# 2_ZEGAR_NIXIE.net
KiCad netlist of a schematic drawn in EAGLE
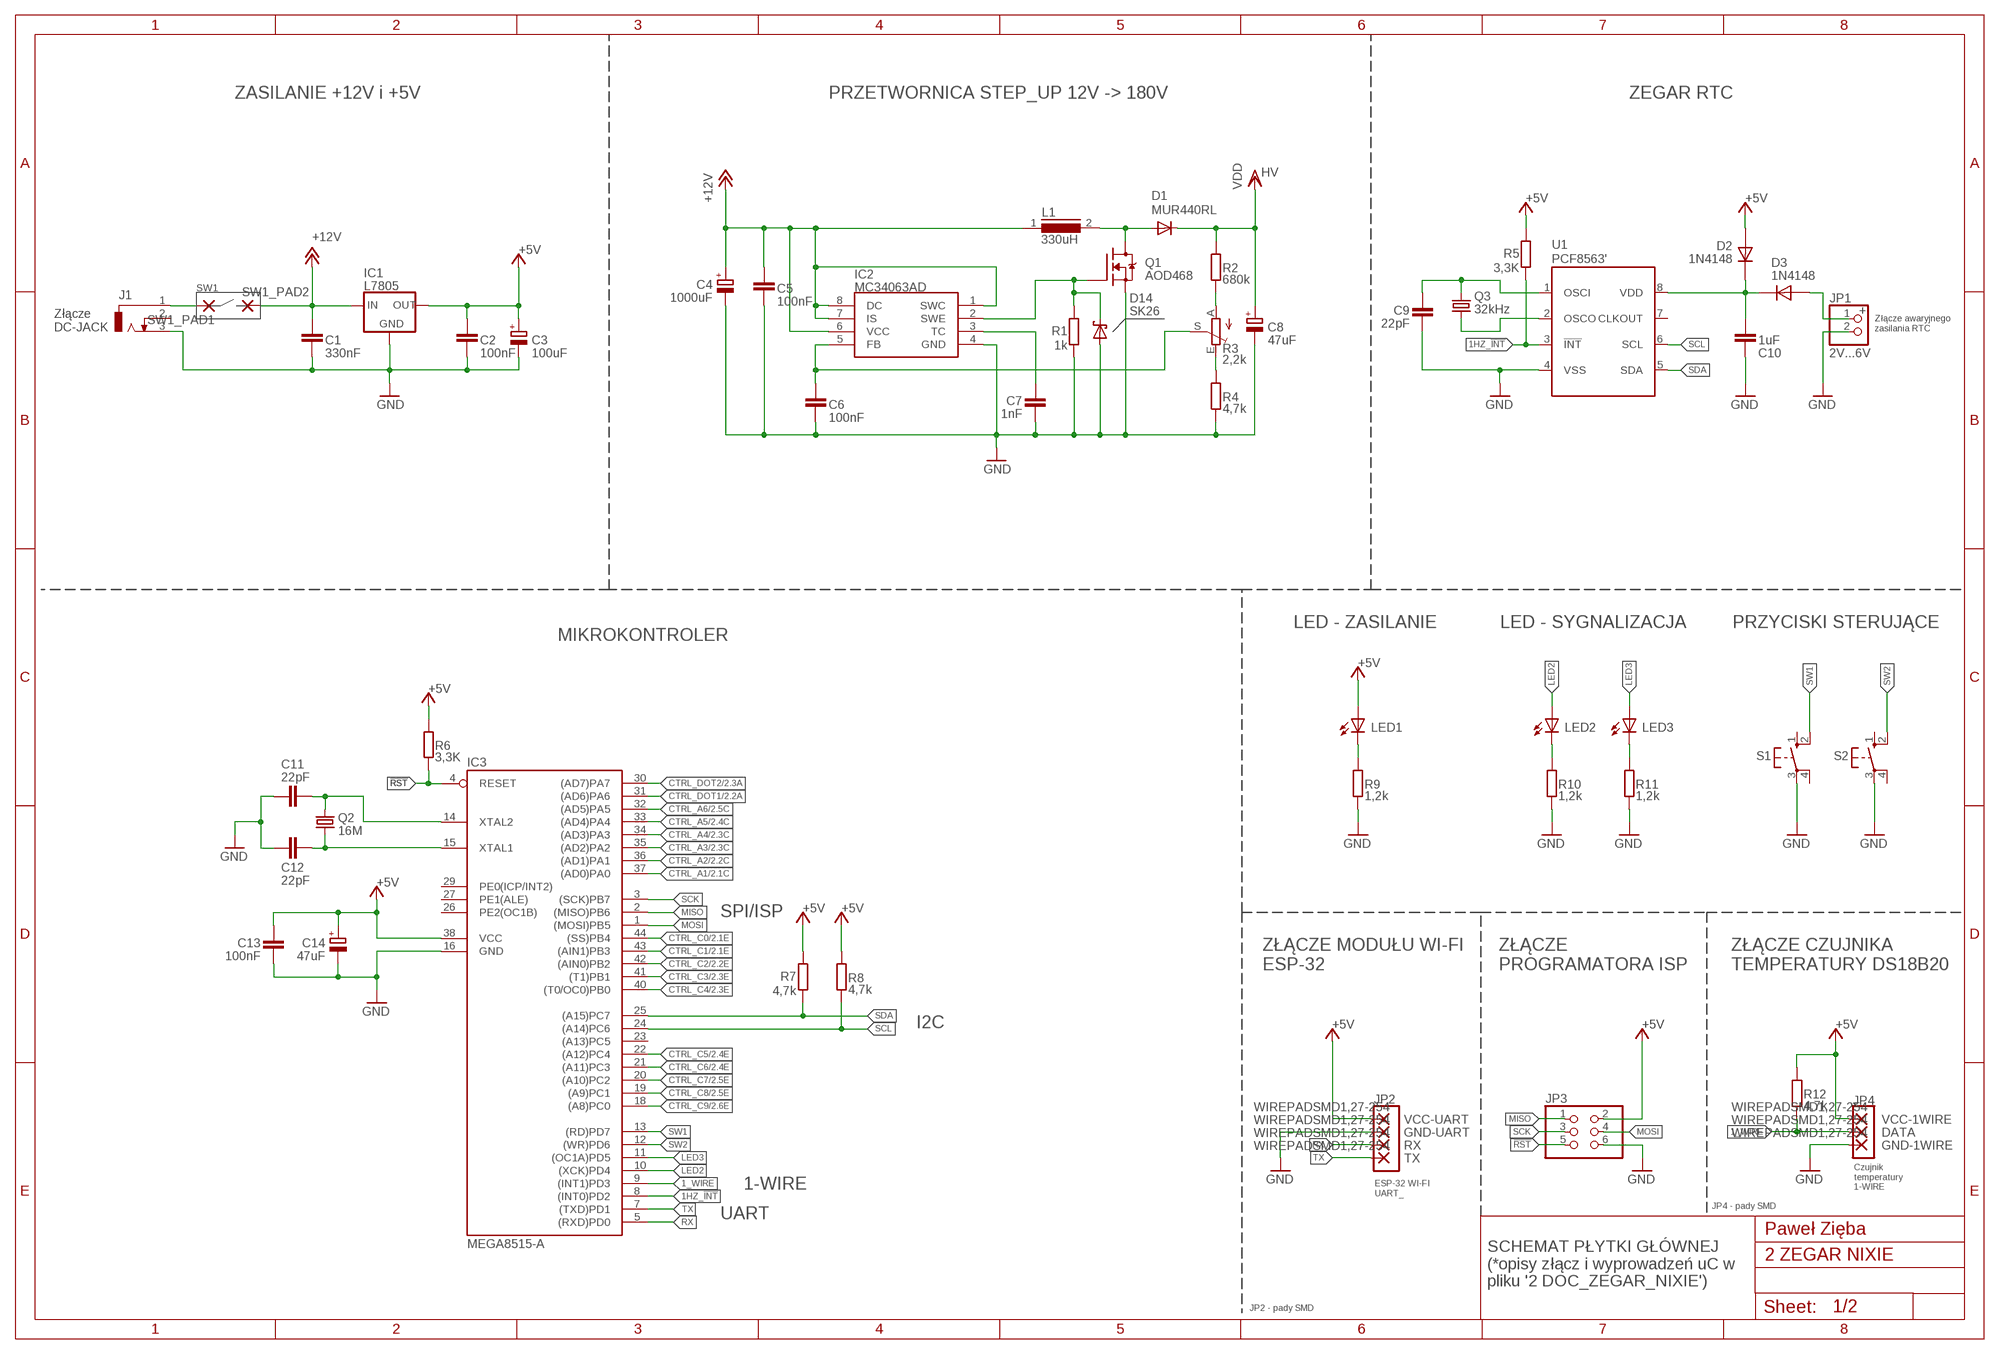
[diagram p0: schematic, sheet 1]
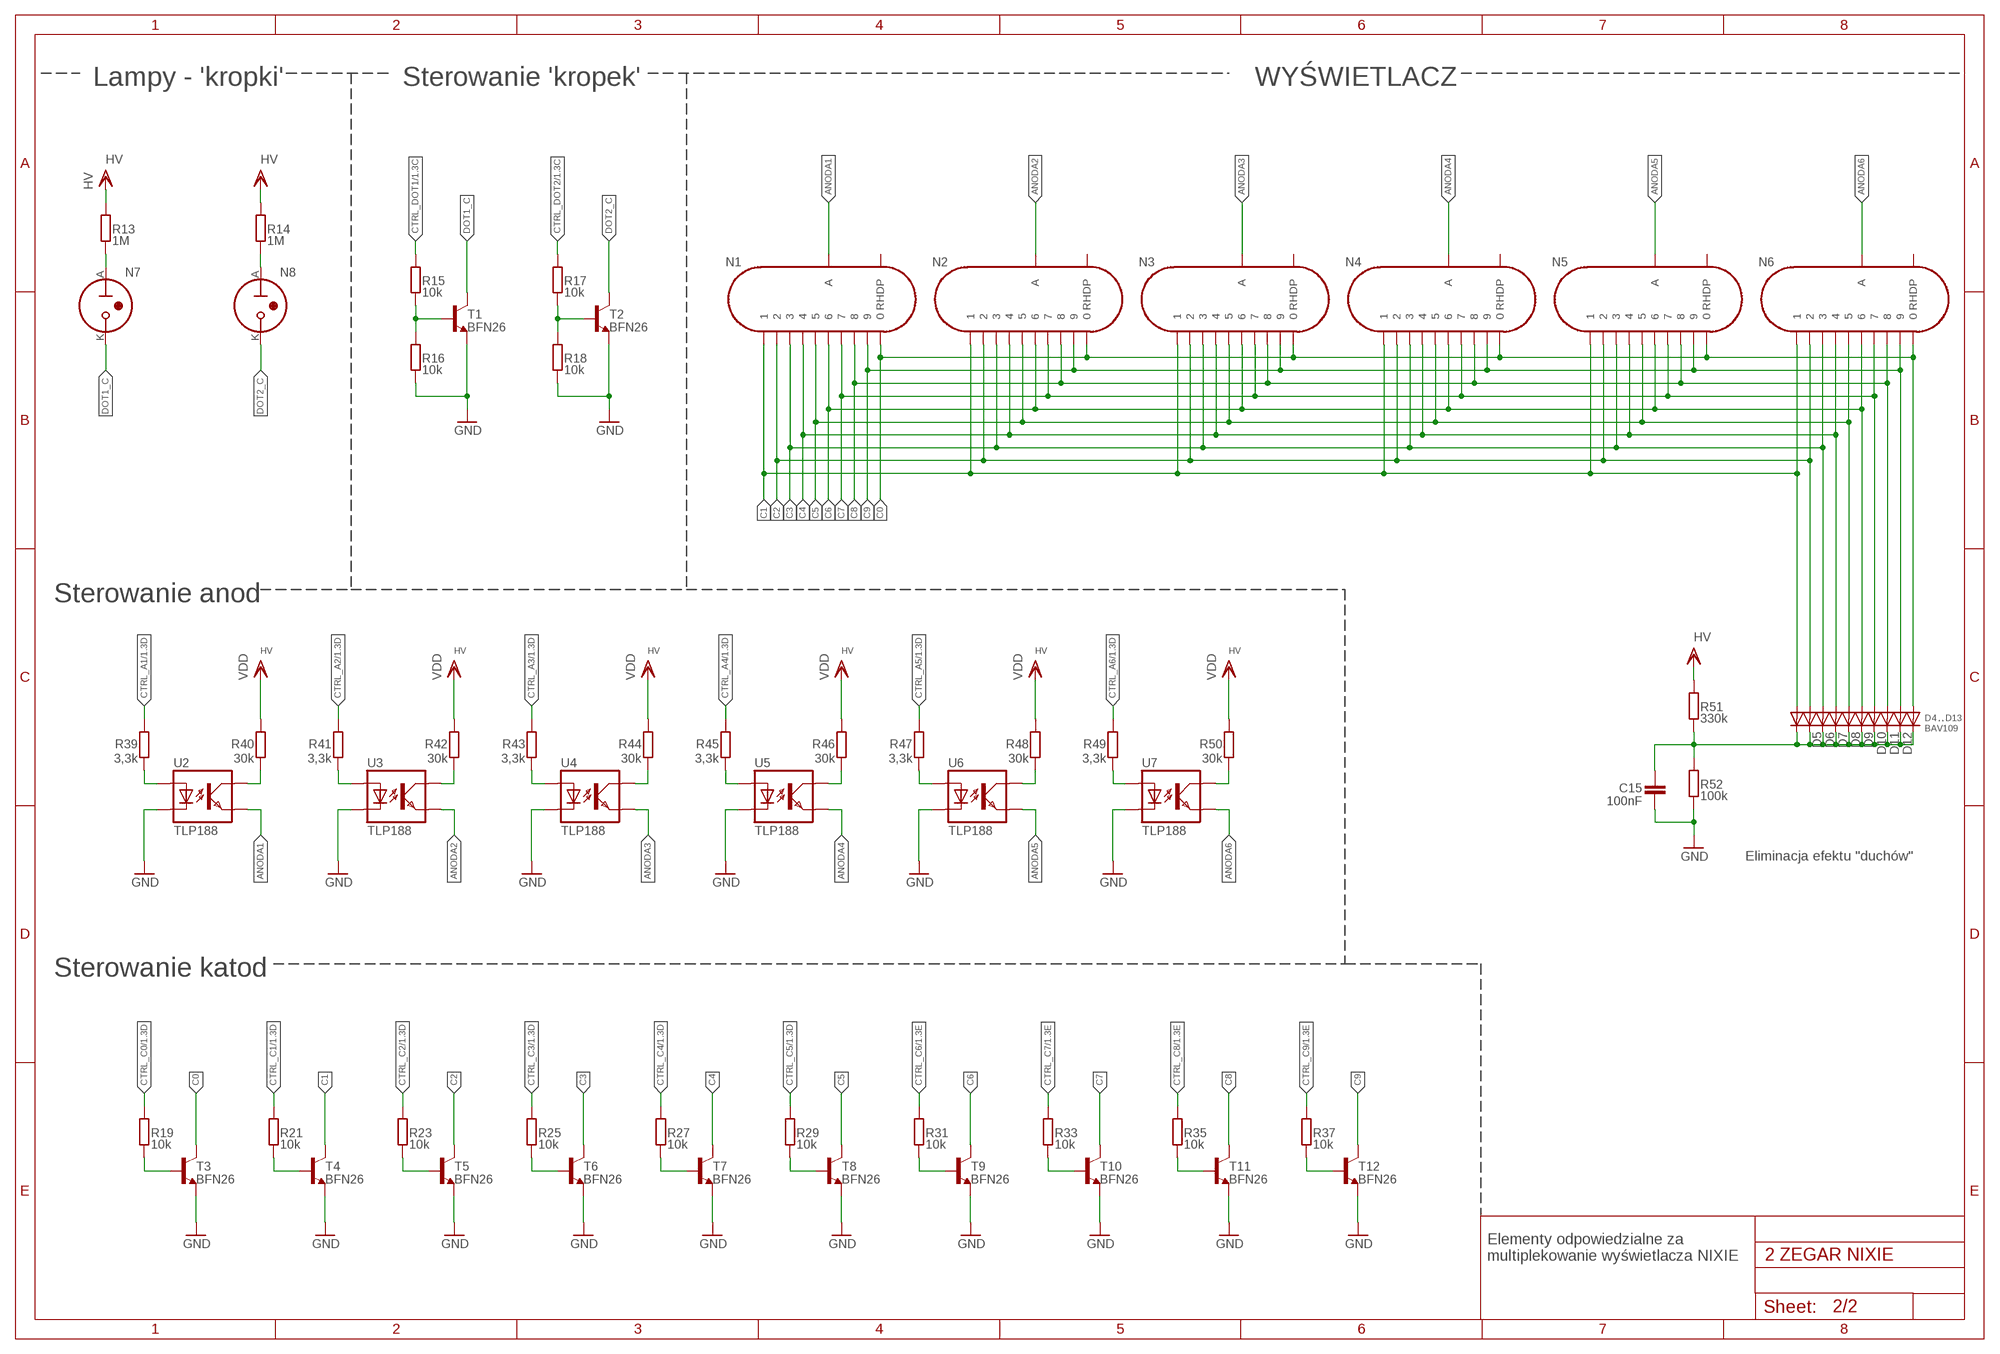
[diagram p1: schematic, sheet 2]

(export (version "E")
  (design (tool "Eeschema 10.0.6"))
  (components
    (comp (ref "C1")
      (value "330nF")
      (footprint "eagle-import:C1206")
      (libsource (lib "eagle-import") (part "C-EUC1206"))
    )
    (comp (ref "C2")
      (value "100nF")
      (footprint "eagle-import:C1206")
      (libsource (lib "eagle-import") (part "C-EUC1206"))
    )
    (comp (ref "C3")
      (value "100uF")
      (footprint "eagle-import:E5-10,5")
      (libsource (lib "eagle-import") (part "CPOL-EUE5-10.5"))
    )
    (comp (ref "C4")
      (value "1000uF")
      (footprint "eagle-import:E5-10,5")
      (libsource (lib "eagle-import") (part "CPOL-EUE5-10.5"))
    )
    (comp (ref "C5")
      (value "100nF")
      (footprint "eagle-import:C1206")
      (libsource (lib "eagle-import") (part "C-EUC1206"))
    )
    (comp (ref "C6")
      (value "100nF")
      (footprint "eagle-import:C1206")
      (libsource (lib "eagle-import") (part "C-EUC1206"))
    )
    (comp (ref "C7")
      (value "1nF")
      (footprint "eagle-import:C1206")
      (libsource (lib "eagle-import") (part "C-EUC1206"))
    )
    (comp (ref "C8")
      (value "47uF")
      (footprint "eagle-import:E5-13")
      (libsource (lib "eagle-import") (part "CPOL-EUE5-13"))
    )
    (comp (ref "C9")
      (value "22pF")
      (footprint "eagle-import:C1206")
      (libsource (lib "eagle-import") (part "C-EUC1206"))
    )
    (comp (ref "C10")
      (value "1uF")
      (footprint "eagle-import:C1206")
      (libsource (lib "eagle-import") (part "C-EUC1206"))
    )
    (comp (ref "C11")
      (value "22pF")
      (footprint "eagle-import:C1206")
      (libsource (lib "eagle-import") (part "C-EUC1206"))
    )
    (comp (ref "C12")
      (value "22pF")
      (footprint "eagle-import:C1206")
      (libsource (lib "eagle-import") (part "C-EUC1206"))
    )
    (comp (ref "C13")
      (value "100nF")
      (footprint "eagle-import:C1206")
      (libsource (lib "eagle-import") (part "C-EUC1206"))
    )
    (comp (ref "C14")
      (value "47uF")
      (footprint "eagle-import:UD-6,3X5,8_NICHICON")
      (libsource (lib "eagle-import") (part "CPOL-EUUD-6,3X8,8"))
    )
    (comp (ref "D1")
      (value "MUR440RL")
      (footprint "eagle-import:C2673")
      (libsource (lib "eagle-import") (part "MUR440RL"))
    )
    (comp (ref "D2")
      (value "1N4148")
      (footprint "eagle-import:D1206")
      (libsource (lib "eagle-import") (part "N14148'"))
    )
    (comp (ref "D3")
      (value "1N4148")
      (footprint "eagle-import:D1206")
      (libsource (lib "eagle-import") (part "N14148'"))
    )
    (comp (ref "D14")
      (value "SK26")
      (footprint "eagle-import:SMB")
      (libsource (lib "eagle-import") (part "SCHOTTKY-DIODESMD"))
    )
    (comp (ref "DATA")
      (value "WIREPADSMD1,27-254")
      (footprint "eagle-import:SMD1,27-2,54")
      (libsource (lib "eagle-import") (part "WIREPADSMD1,27-254"))
    )
    (comp (ref "GND-1WIRE")
      (value "WIREPADSMD1,27-254")
      (footprint "eagle-import:SMD1,27-2,54")
      (libsource (lib "eagle-import") (part "WIREPADSMD1,27-254"))
    )
    (comp (ref "GND-UART")
      (value "WIREPADSMD1,27-254")
      (footprint "eagle-import:SMD1,27-2,54")
      (libsource (lib "eagle-import") (part "WIREPADSMD1,27-254"))
    )
    (comp (ref "IC1")
      (value "L7805")
      (footprint "eagle-import:DPAK")
      (libsource (lib "eagle-import") (part "L78-ST'"))
    )
    (comp (ref "IC2")
      (value "MC34063AD")
      (footprint "eagle-import:SOIC8")
      (libsource (lib "eagle-import") (part "MC34063AD"))
    )
    (comp (ref "IC3")
      (value "MEGA8515-A")
      (footprint "eagle-import:TQFP44")
      (fields (field (name "MPN") "ATMEGA8515-16AU"))
      (libsource (lib "eagle-import") (part "MEGA8515-A"))
    )
    (comp (ref "J1")
      (value "DCJ0303")
      (footprint "eagle-import:DCJ0303")
      (libsource (lib "eagle-import") (part "DCJ0303"))
    )
    (comp (ref "JP1")
      (value "2V...6V")
      (footprint "eagle-import:1X02")
      (libsource (lib "eagle-import") (part "PINHD-1X2"))
    )
    (comp (ref "JP3")
      (value "PINHD-2X3")
      (footprint "eagle-import:2X03")
      (libsource (lib "eagle-import") (part "PINHD-2X3"))
    )
    (comp (ref "L1")
      (value "330uH")
      (footprint "eagle-import:SFT830D")
      (libsource (lib "eagle-import") (part "SFT830D"))
    )
    (comp (ref "LED1")
      (value "LED_E")
      (footprint "eagle-import:LED_1206")
      (libsource (lib "eagle-import") (part "LED_E"))
    )
    (comp (ref "LED2")
      (value "LED_E")
      (footprint "eagle-import:LED_1206")
      (libsource (lib "eagle-import") (part "LED_E"))
    )
    (comp (ref "LED3")
      (value "LED_E")
      (footprint "eagle-import:LED_1206")
      (libsource (lib "eagle-import") (part "LED_E"))
    )
    (comp (ref "Q1")
      (value "AOD468")
      (footprint "eagle-import:DPAK-TO252")
      (libsource (lib "eagle-import") (part "AOD468"))
    )
    (comp (ref "Q2")
      (value "16M")
      (footprint "eagle-import:2.5X2.0_KX-6")
      (libsource (lib "eagle-import") (part "KX-6"))
    )
    (comp (ref "Q3")
      (value "32kHz")
      (footprint "eagle-import:TC26H")
      (libsource (lib "eagle-import") (part "CRYSTALTC26H"))
    )
    (comp (ref "R1")
      (value "1k")
      (footprint "eagle-import:R0805")
      (libsource (lib "eagle-import") (part "R-EU_R0805"))
    )
    (comp (ref "R2")
      (value "680k")
      (footprint "eagle-import:R0805")
      (libsource (lib "eagle-import") (part "R-EU_R0805"))
    )
    (comp (ref "R3")
      (value "2,2k")
      (footprint "eagle-import:CA6V")
      (libsource (lib "eagle-import") (part "TRIM_EU-CA6V"))
    )
    (comp (ref "R4")
      (value "4,7k")
      (footprint "eagle-import:R0805")
      (libsource (lib "eagle-import") (part "R-EU_R0805"))
    )
    (comp (ref "R5")
      (value "3,3K")
      (footprint "eagle-import:R1206")
      (libsource (lib "eagle-import") (part "R-EU_R1206"))
    )
    (comp (ref "R6")
      (value "3,3K")
      (footprint "eagle-import:R1206")
      (libsource (lib "eagle-import") (part "R-EU_R1206"))
    )
    (comp (ref "R7")
      (value "4,7k")
      (footprint "eagle-import:R1206")
      (libsource (lib "eagle-import") (part "R-EU_R1206"))
    )
    (comp (ref "R8")
      (value "4,7k")
      (footprint "eagle-import:R1206")
      (libsource (lib "eagle-import") (part "R-EU_R1206"))
    )
    (comp (ref "R9")
      (value "1,2k")
      (footprint "eagle-import:R1206")
      (libsource (lib "eagle-import") (part "R-EU_R1206"))
    )
    (comp (ref "R10")
      (value "1,2k")
      (footprint "eagle-import:R1206")
      (libsource (lib "eagle-import") (part "R-EU_R1206"))
    )
    (comp (ref "R11")
      (value "1,2k")
      (footprint "eagle-import:R1206")
      (libsource (lib "eagle-import") (part "R-EU_R1206"))
    )
    (comp (ref "R12")
      (value "4,7k")
      (footprint "eagle-import:R1206")
      (libsource (lib "eagle-import") (part "R-EU_R1206"))
    )
    (comp (ref "RX")
      (value "WIREPADSMD1,27-254")
      (footprint "eagle-import:SMD1,27-2,54")
      (libsource (lib "eagle-import") (part "WIREPADSMD1,27-254"))
    )
    (comp (ref "S1")
      (value "10-XX")
      (footprint "eagle-import:B3F-10XX")
      (fields (field (name "MPN") "B3F-1000"))
      (libsource (lib "eagle-import") (part "10-XX"))
    )
    (comp (ref "S2")
      (value "10-XX")
      (footprint "eagle-import:B3F-10XX")
      (fields (field (name "MPN") "B3F-1000"))
      (libsource (lib "eagle-import") (part "10-XX"))
    )
    (comp (ref "SW1_PAD1")
      (value "3,81/1,4")
      (footprint "eagle-import:3,81_1,4")
      (libsource (lib "eagle-import") (part "3,81/1,4"))
    )
    (comp (ref "SW1_PAD2")
      (value "3,81/1,4")
      (footprint "eagle-import:3,81_1,4")
      (libsource (lib "eagle-import") (part "3,81/1,4"))
    )
    (comp (ref "TX")
      (value "WIREPADSMD1,27-254")
      (footprint "eagle-import:SMD1,27-2,54")
      (libsource (lib "eagle-import") (part "WIREPADSMD1,27-254"))
    )
    (comp (ref "U1")
      (value "PCF8563'")
      (footprint "eagle-import:SO08-IRF")
      (libsource (lib "eagle-import") (part "PCF8563'"))
    )
    (comp (ref "VCC-1WIRE")
      (value "WIREPADSMD1,27-254")
      (footprint "eagle-import:SMD1,27-2,54")
      (libsource (lib "eagle-import") (part "WIREPADSMD1,27-254"))
    )
    (comp (ref "VCC-UART")
      (value "WIREPADSMD1,27-254")
      (footprint "eagle-import:SMD1,27-2,54")
      (libsource (lib "eagle-import") (part "WIREPADSMD1,27-254"))
    )
    (comp (ref "C15")
      (value "100nF")
      (footprint "eagle-import:C1206")
      (libsource (lib "eagle-import") (part "C-EUC1206"))
    )
    (comp (ref "D4")
      (value "DIODE-MINIMELF")
      (footprint "eagle-import:MINIMELF")
      (libsource (lib "eagle-import") (part "DIODE-MINIMELF"))
    )
    (comp (ref "D5")
      (value "DIODE-MINIMELF")
      (footprint "eagle-import:MINIMELF")
      (libsource (lib "eagle-import") (part "DIODE-MINIMELF"))
    )
    (comp (ref "D6")
      (value "DIODE-MINIMELF")
      (footprint "eagle-import:MINIMELF")
      (libsource (lib "eagle-import") (part "DIODE-MINIMELF"))
    )
    (comp (ref "D7")
      (value "DIODE-MINIMELF")
      (footprint "eagle-import:MINIMELF")
      (libsource (lib "eagle-import") (part "DIODE-MINIMELF"))
    )
    (comp (ref "D8")
      (value "DIODE-MINIMELF")
      (footprint "eagle-import:MINIMELF")
      (libsource (lib "eagle-import") (part "DIODE-MINIMELF"))
    )
    (comp (ref "D9")
      (value "DIODE-MINIMELF")
      (footprint "eagle-import:MINIMELF")
      (libsource (lib "eagle-import") (part "DIODE-MINIMELF"))
    )
    (comp (ref "D10")
      (value "DIODE-MINIMELF")
      (footprint "eagle-import:MINIMELF")
      (libsource (lib "eagle-import") (part "DIODE-MINIMELF"))
    )
    (comp (ref "D11")
      (value "DIODE-MINIMELF")
      (footprint "eagle-import:MINIMELF")
      (libsource (lib "eagle-import") (part "DIODE-MINIMELF"))
    )
    (comp (ref "D12")
      (value "DIODE-MINIMELF")
      (footprint "eagle-import:MINIMELF")
      (libsource (lib "eagle-import") (part "DIODE-MINIMELF"))
    )
    (comp (ref "D13")
      (value "BAV109")
      (footprint "eagle-import:MINIMELF")
      (libsource (lib "eagle-import") (part "DIODE-MINIMELF"))
    )
    (comp (ref "N1")
      (value "IN-8-2")
      (footprint "eagle-import:IN-8-2")
      (libsource (lib "eagle-import") (part "IN-8-2"))
    )
    (comp (ref "N2")
      (value "IN-8-2")
      (footprint "eagle-import:IN-8-2")
      (libsource (lib "eagle-import") (part "IN-8-2"))
    )
    (comp (ref "N3")
      (value "IN-8-2")
      (footprint "eagle-import:IN-8-2")
      (libsource (lib "eagle-import") (part "IN-8-2"))
    )
    (comp (ref "N4")
      (value "IN-8-2")
      (footprint "eagle-import:IN-8-2")
      (libsource (lib "eagle-import") (part "IN-8-2"))
    )
    (comp (ref "N5")
      (value "IN-8-2")
      (footprint "eagle-import:IN-8-2")
      (libsource (lib "eagle-import") (part "IN-8-2"))
    )
    (comp (ref "N6")
      (value "IN-8-2")
      (footprint "eagle-import:IN-8-2")
      (libsource (lib "eagle-import") (part "IN-8-2"))
    )
    (comp (ref "N7")
      (value "IN-3")
      (footprint "eagle-import:IN-3")
      (libsource (lib "eagle-import") (part "IN-3"))
    )
    (comp (ref "N8")
      (value "IN-3")
      (footprint "eagle-import:IN-3")
      (libsource (lib "eagle-import") (part "IN-3"))
    )
    (comp (ref "R13")
      (value "1M")
      (footprint "eagle-import:R1206")
      (libsource (lib "eagle-import") (part "R-EU_R1206"))
    )
    (comp (ref "R14")
      (value "1M")
      (footprint "eagle-import:R1206")
      (libsource (lib "eagle-import") (part "R-EU_R1206"))
    )
    (comp (ref "R15")
      (value "10k")
      (footprint "eagle-import:R0805")
      (libsource (lib "eagle-import") (part "R-EU_R0805"))
    )
    (comp (ref "R16")
      (value "10k")
      (footprint "eagle-import:R0805")
      (libsource (lib "eagle-import") (part "R-EU_R0805"))
    )
    (comp (ref "R17")
      (value "10k")
      (footprint "eagle-import:R0805")
      (libsource (lib "eagle-import") (part "R-EU_R0805"))
    )
    (comp (ref "R18")
      (value "10k")
      (footprint "eagle-import:R0805")
      (libsource (lib "eagle-import") (part "R-EU_R0805"))
    )
    (comp (ref "R19")
      (value "10k")
      (footprint "eagle-import:R0805")
      (libsource (lib "eagle-import") (part "R-EU_R0805"))
    )
    (comp (ref "R21")
      (value "10k")
      (footprint "eagle-import:R0805")
      (libsource (lib "eagle-import") (part "R-EU_R0805"))
    )
    (comp (ref "R23")
      (value "10k")
      (footprint "eagle-import:R0805")
      (libsource (lib "eagle-import") (part "R-EU_R0805"))
    )
    (comp (ref "R25")
      (value "10k")
      (footprint "eagle-import:R0805")
      (libsource (lib "eagle-import") (part "R-EU_R0805"))
    )
    (comp (ref "R27")
      (value "10k")
      (footprint "eagle-import:R0805")
      (libsource (lib "eagle-import") (part "R-EU_R0805"))
    )
    (comp (ref "R29")
      (value "10k")
      (footprint "eagle-import:R0805")
      (libsource (lib "eagle-import") (part "R-EU_R0805"))
    )
    (comp (ref "R31")
      (value "10k")
      (footprint "eagle-import:R0805")
      (libsource (lib "eagle-import") (part "R-EU_R0805"))
    )
    (comp (ref "R33")
      (value "10k")
      (footprint "eagle-import:R0805")
      (libsource (lib "eagle-import") (part "R-EU_R0805"))
    )
    (comp (ref "R35")
      (value "10k")
      (footprint "eagle-import:R0805")
      (libsource (lib "eagle-import") (part "R-EU_R0805"))
    )
    (comp (ref "R37")
      (value "10k")
      (footprint "eagle-import:R0805")
      (libsource (lib "eagle-import") (part "R-EU_R0805"))
    )
    (comp (ref "R39")
      (value "3,3k")
      (footprint "eagle-import:R0805")
      (libsource (lib "eagle-import") (part "R-EU_R0805"))
    )
    (comp (ref "R40")
      (value "30k")
      (footprint "eagle-import:R1206")
      (libsource (lib "eagle-import") (part "R-EU_R1206"))
    )
    (comp (ref "R41")
      (value "3,3k")
      (footprint "eagle-import:R0805")
      (libsource (lib "eagle-import") (part "R-EU_R0805"))
    )
    (comp (ref "R42")
      (value "30k")
      (footprint "eagle-import:R1206")
      (libsource (lib "eagle-import") (part "R-EU_R1206"))
    )
    (comp (ref "R43")
      (value "3,3k")
      (footprint "eagle-import:R0805")
      (libsource (lib "eagle-import") (part "R-EU_R0805"))
    )
    (comp (ref "R44")
      (value "30k")
      (footprint "eagle-import:R1206")
      (libsource (lib "eagle-import") (part "R-EU_R1206"))
    )
    (comp (ref "R45")
      (value "3,3k")
      (footprint "eagle-import:R0805")
      (libsource (lib "eagle-import") (part "R-EU_R0805"))
    )
    (comp (ref "R46")
      (value "30k")
      (footprint "eagle-import:R1206")
      (libsource (lib "eagle-import") (part "R-EU_R1206"))
    )
    (comp (ref "R47")
      (value "3,3k")
      (footprint "eagle-import:R0805")
      (libsource (lib "eagle-import") (part "R-EU_R0805"))
    )
    (comp (ref "R48")
      (value "30k")
      (footprint "eagle-import:R1206")
      (libsource (lib "eagle-import") (part "R-EU_R1206"))
    )
    (comp (ref "R49")
      (value "3,3k")
      (footprint "eagle-import:R0805")
      (libsource (lib "eagle-import") (part "R-EU_R0805"))
    )
    (comp (ref "R50")
      (value "30k")
      (footprint "eagle-import:R1206")
      (libsource (lib "eagle-import") (part "R-EU_R1206"))
    )
    (comp (ref "R51")
      (value "330k")
      (footprint "eagle-import:R1206")
      (libsource (lib "eagle-import") (part "R-EU_R1206"))
    )
    (comp (ref "R52")
      (value "100k")
      (footprint "eagle-import:R1206")
      (libsource (lib "eagle-import") (part "R-EU_R1206"))
    )
    (comp (ref "T1")
      (value "BFN26")
      (footprint "eagle-import:SOT23-BEC")
      (libsource (lib "eagle-import") (part "BC850SMD"))
    )
    (comp (ref "T2")
      (value "BFN26")
      (footprint "eagle-import:SOT23-BEC")
      (libsource (lib "eagle-import") (part "BC850SMD"))
    )
    (comp (ref "T3")
      (value "BFN26")
      (footprint "eagle-import:SOT23-BEC")
      (libsource (lib "eagle-import") (part "BC850SMD"))
    )
    (comp (ref "T4")
      (value "BFN26")
      (footprint "eagle-import:SOT23-BEC")
      (libsource (lib "eagle-import") (part "BC850SMD"))
    )
    (comp (ref "T5")
      (value "BFN26")
      (footprint "eagle-import:SOT23-BEC")
      (libsource (lib "eagle-import") (part "BC850SMD"))
    )
    (comp (ref "T6")
      (value "BFN26")
      (footprint "eagle-import:SOT23-BEC")
      (libsource (lib "eagle-import") (part "BC850SMD"))
    )
    (comp (ref "T7")
      (value "BFN26")
      (footprint "eagle-import:SOT23-BEC")
      (libsource (lib "eagle-import") (part "BC850SMD"))
    )
    (comp (ref "T8")
      (value "BFN26")
      (footprint "eagle-import:SOT23-BEC")
      (libsource (lib "eagle-import") (part "BC850SMD"))
    )
    (comp (ref "T9")
      (value "BFN26")
      (footprint "eagle-import:SOT23-BEC")
      (libsource (lib "eagle-import") (part "BC850SMD"))
    )
    (comp (ref "T10")
      (value "BFN26")
      (footprint "eagle-import:SOT23-BEC")
      (libsource (lib "eagle-import") (part "BC850SMD"))
    )
    (comp (ref "T11")
      (value "BFN26")
      (footprint "eagle-import:SOT23-BEC")
      (libsource (lib "eagle-import") (part "BC850SMD"))
    )
    (comp (ref "T12")
      (value "BFN26")
      (footprint "eagle-import:SOT23-BEC")
      (libsource (lib "eagle-import") (part "BC850SMD"))
    )
    (comp (ref "U2")
      (value "TLP188")
      (footprint "eagle-import:11-4M1S")
      (libsource (lib "eagle-import") (part "TLP188"))
    )
    (comp (ref "U3")
      (value "TLP188")
      (footprint "eagle-import:11-4M1S")
      (libsource (lib "eagle-import") (part "TLP188"))
    )
    (comp (ref "U4")
      (value "TLP188")
      (footprint "eagle-import:11-4M1S")
      (libsource (lib "eagle-import") (part "TLP188"))
    )
    (comp (ref "U5")
      (value "TLP188")
      (footprint "eagle-import:11-4M1S")
      (libsource (lib "eagle-import") (part "TLP188"))
    )
    (comp (ref "U6")
      (value "TLP188")
      (footprint "eagle-import:11-4M1S")
      (libsource (lib "eagle-import") (part "TLP188"))
    )
    (comp (ref "U7")
      (value "TLP188")
      (footprint "eagle-import:11-4M1S")
      (libsource (lib "eagle-import") (part "TLP188"))
    )
  )
  (nets
    (net (code "1") (name "+5V") (class "Default")
      (node (ref "C13") (pin "2") (pinfunction "2_2") (pintype "passive"))
      (node (ref "C14") (pin "+") (pinfunction "+_+") (pintype "passive"))
      (node (ref "C2") (pin "1") (pinfunction "1_1") (pintype "passive"))
      (node (ref "C3") (pin "+") (pinfunction "+_+") (pintype "passive"))
      (node (ref "D2") (pin "1") (pinfunction "+_1") (pintype "bidirectional"))
      (node (ref "IC1") (pin "3") (pinfunction "OUT_3") (pintype "passive"))
      (node (ref "IC3") (pin "38") (pinfunction "VCC_38") (pintype "power_in"))
      (node (ref "JP3") (pin "2") (pinfunction "2_2") (pintype "passive"))
      (node (ref "LED1") (pin "A") (pinfunction "A_A") (pintype "passive"))
      (node (ref "R12") (pin "2") (pinfunction "2_2") (pintype "passive"))
      (node (ref "R5") (pin "2") (pinfunction "2_2") (pintype "passive"))
      (node (ref "R6") (pin "2") (pinfunction "2_2") (pintype "passive"))
      (node (ref "R7") (pin "2") (pinfunction "2_2") (pintype "passive"))
      (node (ref "R8") (pin "2") (pinfunction "2_2") (pintype "passive"))
      (node (ref "VCC-1WIRE") (pin "1") (pinfunction "P_1") (pintype "passive"))
      (node (ref "VCC-UART") (pin "1") (pinfunction "P_1") (pintype "passive"))
    )
    (net (code "2") (name "+12V") (class "Default")
      (node (ref "C1") (pin "1") (pinfunction "1_1") (pintype "passive"))
      (node (ref "C4") (pin "+") (pinfunction "+_+") (pintype "passive"))
      (node (ref "C5") (pin "1") (pinfunction "1_1") (pintype "passive"))
      (node (ref "IC1") (pin "1") (pinfunction "IN_1") (pintype "input"))
      (node (ref "IC2") (pin "1") (pinfunction "SWC_1") (pintype "passive"))
      (node (ref "IC2") (pin "6") (pinfunction "VCC_6") (pintype "passive"))
      (node (ref "IC2") (pin "7") (pinfunction "IS_7") (pintype "passive"))
      (node (ref "IC2") (pin "8") (pinfunction "DC_8") (pintype "passive"))
      (node (ref "L1") (pin "1") (pinfunction "1_1") (pintype "passive"))
      (node (ref "SW1_PAD2") (pin "1") (pinfunction "P_1") (pintype "passive"))
    )
    (net (code "3") (name "1HZ_~{INT}") (class "Default")
      (node (ref "IC3") (pin "8") (pinfunction "(INT0)PD2_8") (pintype "bidirectional"))
      (node (ref "R5") (pin "1") (pinfunction "1_1") (pintype "passive"))
      (node (ref "U1") (pin "3") (pinfunction "~{INT}_3") (pintype "bidirectional"))
    )
    (net (code "4") (name "1_WIRE") (class "Default")
      (node (ref "DATA") (pin "1") (pinfunction "P_1") (pintype "passive"))
      (node (ref "IC3") (pin "9") (pinfunction "(INT1)PD3_9") (pintype "bidirectional"))
      (node (ref "R12") (pin "1") (pinfunction "1_1") (pintype "passive"))
    )
    (net (code "5") (name "ANODA1") (class "Default")
      (node (ref "N1") (pin "A") (pinfunction "A_A") (pintype "bidirectional"))
      (node (ref "U2") (pin "P$4") (pinfunction "EMIT_P$4") (pintype "passive"))
    )
    (net (code "6") (name "ANODA2") (class "Default")
      (node (ref "N2") (pin "A") (pinfunction "A_A") (pintype "bidirectional"))
      (node (ref "U3") (pin "P$4") (pinfunction "EMIT_P$4") (pintype "passive"))
    )
    (net (code "7") (name "ANODA3") (class "Default")
      (node (ref "N3") (pin "A") (pinfunction "A_A") (pintype "bidirectional"))
      (node (ref "U4") (pin "P$4") (pinfunction "EMIT_P$4") (pintype "passive"))
    )
    (net (code "8") (name "ANODA4") (class "Default")
      (node (ref "N4") (pin "A") (pinfunction "A_A") (pintype "bidirectional"))
      (node (ref "U5") (pin "P$4") (pinfunction "EMIT_P$4") (pintype "passive"))
    )
    (net (code "9") (name "ANODA5") (class "Default")
      (node (ref "N5") (pin "A") (pinfunction "A_A") (pintype "bidirectional"))
      (node (ref "U6") (pin "P$4") (pinfunction "EMIT_P$4") (pintype "passive"))
    )
    (net (code "10") (name "ANODA6") (class "Default")
      (node (ref "N6") (pin "A") (pinfunction "A_A") (pintype "bidirectional"))
      (node (ref "U7") (pin "P$4") (pinfunction "EMIT_P$4") (pintype "passive"))
    )
    (net (code "11") (name "C0") (class "Default")
      (node (ref "D13") (pin "A") (pinfunction "A_A") (pintype "passive"))
      (node (ref "N1") (pin "0") (pinfunction "0_0") (pintype "bidirectional"))
      (node (ref "N2") (pin "0") (pinfunction "0_0") (pintype "bidirectional"))
      (node (ref "N3") (pin "0") (pinfunction "0_0") (pintype "bidirectional"))
      (node (ref "N4") (pin "0") (pinfunction "0_0") (pintype "bidirectional"))
      (node (ref "N5") (pin "0") (pinfunction "0_0") (pintype "bidirectional"))
      (node (ref "N6") (pin "0") (pinfunction "0_0") (pintype "bidirectional"))
      (node (ref "T3") (pin "C") (pinfunction "C_C") (pintype "passive"))
    )
    (net (code "12") (name "C1") (class "Default")
      (node (ref "D4") (pin "A") (pinfunction "A_A") (pintype "passive"))
      (node (ref "N1") (pin "1") (pinfunction "1_1") (pintype "bidirectional"))
      (node (ref "N2") (pin "1") (pinfunction "1_1") (pintype "bidirectional"))
      (node (ref "N3") (pin "1") (pinfunction "1_1") (pintype "bidirectional"))
      (node (ref "N4") (pin "1") (pinfunction "1_1") (pintype "bidirectional"))
      (node (ref "N5") (pin "1") (pinfunction "1_1") (pintype "bidirectional"))
      (node (ref "N6") (pin "1") (pinfunction "1_1") (pintype "bidirectional"))
      (node (ref "T4") (pin "C") (pinfunction "C_C") (pintype "passive"))
    )
    (net (code "13") (name "C2") (class "Default")
      (node (ref "D5") (pin "A") (pinfunction "A_A") (pintype "passive"))
      (node (ref "N1") (pin "2") (pinfunction "2_2") (pintype "bidirectional"))
      (node (ref "N2") (pin "2") (pinfunction "2_2") (pintype "bidirectional"))
      (node (ref "N3") (pin "2") (pinfunction "2_2") (pintype "bidirectional"))
      (node (ref "N4") (pin "2") (pinfunction "2_2") (pintype "bidirectional"))
      (node (ref "N5") (pin "2") (pinfunction "2_2") (pintype "bidirectional"))
      (node (ref "N6") (pin "2") (pinfunction "2_2") (pintype "bidirectional"))
      (node (ref "T5") (pin "C") (pinfunction "C_C") (pintype "passive"))
    )
    (net (code "14") (name "C3") (class "Default")
      (node (ref "D6") (pin "A") (pinfunction "A_A") (pintype "passive"))
      (node (ref "N1") (pin "3") (pinfunction "3_3") (pintype "bidirectional"))
      (node (ref "N2") (pin "3") (pinfunction "3_3") (pintype "bidirectional"))
      (node (ref "N3") (pin "3") (pinfunction "3_3") (pintype "bidirectional"))
      (node (ref "N4") (pin "3") (pinfunction "3_3") (pintype "bidirectional"))
      (node (ref "N5") (pin "3") (pinfunction "3_3") (pintype "bidirectional"))
      (node (ref "N6") (pin "3") (pinfunction "3_3") (pintype "bidirectional"))
      (node (ref "T6") (pin "C") (pinfunction "C_C") (pintype "passive"))
    )
    (net (code "15") (name "C4") (class "Default")
      (node (ref "D7") (pin "A") (pinfunction "A_A") (pintype "passive"))
      (node (ref "N1") (pin "4") (pinfunction "4_4") (pintype "bidirectional"))
      (node (ref "N2") (pin "4") (pinfunction "4_4") (pintype "bidirectional"))
      (node (ref "N3") (pin "4") (pinfunction "4_4") (pintype "bidirectional"))
      (node (ref "N4") (pin "4") (pinfunction "4_4") (pintype "bidirectional"))
      (node (ref "N5") (pin "4") (pinfunction "4_4") (pintype "bidirectional"))
      (node (ref "N6") (pin "4") (pinfunction "4_4") (pintype "bidirectional"))
      (node (ref "T7") (pin "C") (pinfunction "C_C") (pintype "passive"))
    )
    (net (code "16") (name "C5") (class "Default")
      (node (ref "D8") (pin "A") (pinfunction "A_A") (pintype "passive"))
      (node (ref "N1") (pin "5") (pinfunction "5_5") (pintype "bidirectional"))
      (node (ref "N2") (pin "5") (pinfunction "5_5") (pintype "bidirectional"))
      (node (ref "N3") (pin "5") (pinfunction "5_5") (pintype "bidirectional"))
      (node (ref "N4") (pin "5") (pinfunction "5_5") (pintype "bidirectional"))
      (node (ref "N5") (pin "5") (pinfunction "5_5") (pintype "bidirectional"))
      (node (ref "N6") (pin "5") (pinfunction "5_5") (pintype "bidirectional"))
      (node (ref "T8") (pin "C") (pinfunction "C_C") (pintype "passive"))
    )
    (net (code "17") (name "C6") (class "Default")
      (node (ref "D9") (pin "A") (pinfunction "A_A") (pintype "passive"))
      (node (ref "N1") (pin "6") (pinfunction "6_6") (pintype "bidirectional"))
      (node (ref "N2") (pin "6") (pinfunction "6_6") (pintype "bidirectional"))
      (node (ref "N3") (pin "6") (pinfunction "6_6") (pintype "bidirectional"))
      (node (ref "N4") (pin "6") (pinfunction "6_6") (pintype "bidirectional"))
      (node (ref "N5") (pin "6") (pinfunction "6_6") (pintype "bidirectional"))
      (node (ref "N6") (pin "6") (pinfunction "6_6") (pintype "bidirectional"))
      (node (ref "T9") (pin "C") (pinfunction "C_C") (pintype "passive"))
    )
    (net (code "18") (name "C7") (class "Default")
      (node (ref "D10") (pin "A") (pinfunction "A_A") (pintype "passive"))
      (node (ref "N1") (pin "7") (pinfunction "7_7") (pintype "bidirectional"))
      (node (ref "N2") (pin "7") (pinfunction "7_7") (pintype "bidirectional"))
      (node (ref "N3") (pin "7") (pinfunction "7_7") (pintype "bidirectional"))
      (node (ref "N4") (pin "7") (pinfunction "7_7") (pintype "bidirectional"))
      (node (ref "N5") (pin "7") (pinfunction "7_7") (pintype "bidirectional"))
      (node (ref "N6") (pin "7") (pinfunction "7_7") (pintype "bidirectional"))
      (node (ref "T10") (pin "C") (pinfunction "C_C") (pintype "passive"))
    )
    (net (code "19") (name "C8") (class "Default")
      (node (ref "D11") (pin "A") (pinfunction "A_A") (pintype "passive"))
      (node (ref "N1") (pin "8") (pinfunction "8_8") (pintype "bidirectional"))
      (node (ref "N2") (pin "8") (pinfunction "8_8") (pintype "bidirectional"))
      (node (ref "N3") (pin "8") (pinfunction "8_8") (pintype "bidirectional"))
      (node (ref "N4") (pin "8") (pinfunction "8_8") (pintype "bidirectional"))
      (node (ref "N5") (pin "8") (pinfunction "8_8") (pintype "bidirectional"))
      (node (ref "N6") (pin "8") (pinfunction "8_8") (pintype "bidirectional"))
      (node (ref "T11") (pin "C") (pinfunction "C_C") (pintype "passive"))
    )
    (net (code "20") (name "C9") (class "Default")
      (node (ref "D12") (pin "A") (pinfunction "A_A") (pintype "passive"))
      (node (ref "N1") (pin "9") (pinfunction "9_9") (pintype "bidirectional"))
      (node (ref "N2") (pin "9") (pinfunction "9_9") (pintype "bidirectional"))
      (node (ref "N3") (pin "9") (pinfunction "9_9") (pintype "bidirectional"))
      (node (ref "N4") (pin "9") (pinfunction "9_9") (pintype "bidirectional"))
      (node (ref "N5") (pin "9") (pinfunction "9_9") (pintype "bidirectional"))
      (node (ref "N6") (pin "9") (pinfunction "9_9") (pintype "bidirectional"))
      (node (ref "T12") (pin "C") (pinfunction "C_C") (pintype "passive"))
    )
    (net (code "21") (name "CTRL_A1") (class "Default")
      (node (ref "IC3") (pin "37") (pinfunction "(AD0)PA0_37") (pintype "bidirectional"))
      (node (ref "R39") (pin "1") (pinfunction "1_1") (pintype "passive"))
    )
    (net (code "22") (name "CTRL_A2") (class "Default")
      (node (ref "IC3") (pin "36") (pinfunction "(AD1)PA1_36") (pintype "bidirectional"))
      (node (ref "R41") (pin "1") (pinfunction "1_1") (pintype "passive"))
    )
    (net (code "23") (name "CTRL_A3") (class "Default")
      (node (ref "IC3") (pin "35") (pinfunction "(AD2)PA2_35") (pintype "bidirectional"))
      (node (ref "R43") (pin "1") (pinfunction "1_1") (pintype "passive"))
    )
    (net (code "24") (name "CTRL_A4") (class "Default")
      (node (ref "IC3") (pin "34") (pinfunction "(AD3)PA3_34") (pintype "bidirectional"))
      (node (ref "R45") (pin "1") (pinfunction "1_1") (pintype "passive"))
    )
    (net (code "25") (name "CTRL_A5") (class "Default")
      (node (ref "IC3") (pin "33") (pinfunction "(AD4)PA4_33") (pintype "bidirectional"))
      (node (ref "R47") (pin "1") (pinfunction "1_1") (pintype "passive"))
    )
    (net (code "26") (name "CTRL_A6") (class "Default")
      (node (ref "IC3") (pin "32") (pinfunction "(AD5)PA5_32") (pintype "bidirectional"))
      (node (ref "R49") (pin "1") (pinfunction "1_1") (pintype "passive"))
    )
    (net (code "27") (name "CTRL_C0") (class "Default")
      (node (ref "IC3") (pin "44") (pinfunction "(SS)PB4_44") (pintype "bidirectional"))
      (node (ref "R19") (pin "2") (pinfunction "2_2") (pintype "passive"))
    )
    (net (code "28") (name "CTRL_C1") (class "Default")
      (node (ref "IC3") (pin "43") (pinfunction "(AIN1)PB3_43") (pintype "bidirectional"))
      (node (ref "R21") (pin "2") (pinfunction "2_2") (pintype "passive"))
    )
    (net (code "29") (name "CTRL_C2") (class "Default")
      (node (ref "IC3") (pin "42") (pinfunction "(AIN0)PB2_42") (pintype "bidirectional"))
      (node (ref "R23") (pin "2") (pinfunction "2_2") (pintype "passive"))
    )
    (net (code "30") (name "CTRL_C3") (class "Default")
      (node (ref "IC3") (pin "41") (pinfunction "(T1)PB1_41") (pintype "bidirectional"))
      (node (ref "R25") (pin "2") (pinfunction "2_2") (pintype "passive"))
    )
    (net (code "31") (name "CTRL_C4") (class "Default")
      (node (ref "IC3") (pin "40") (pinfunction "(T0/OC0)PB0_40") (pintype "bidirectional"))
      (node (ref "R27") (pin "2") (pinfunction "2_2") (pintype "passive"))
    )
    (net (code "32") (name "CTRL_C5") (class "Default")
      (node (ref "IC3") (pin "22") (pinfunction "(A12)PC4_22") (pintype "bidirectional"))
      (node (ref "R29") (pin "2") (pinfunction "2_2") (pintype "passive"))
    )
    (net (code "33") (name "CTRL_C6") (class "Default")
      (node (ref "IC3") (pin "21") (pinfunction "(A11)PC3_21") (pintype "bidirectional"))
      (node (ref "R31") (pin "2") (pinfunction "2_2") (pintype "passive"))
    )
    (net (code "34") (name "CTRL_C7") (class "Default")
      (node (ref "IC3") (pin "20") (pinfunction "(A10)PC2_20") (pintype "bidirectional"))
      (node (ref "R33") (pin "2") (pinfunction "2_2") (pintype "passive"))
    )
    (net (code "35") (name "CTRL_C8") (class "Default")
      (node (ref "IC3") (pin "19") (pinfunction "(A9)PC1_19") (pintype "bidirectional"))
      (node (ref "R35") (pin "2") (pinfunction "2_2") (pintype "passive"))
    )
    (net (code "36") (name "CTRL_C9") (class "Default")
      (node (ref "IC3") (pin "18") (pinfunction "(A8)PC0_18") (pintype "bidirectional"))
      (node (ref "R37") (pin "2") (pinfunction "2_2") (pintype "passive"))
    )
    (net (code "37") (name "CTRL_DOT1") (class "Default")
      (node (ref "IC3") (pin "31") (pinfunction "(AD6)PA6_31") (pintype "bidirectional"))
      (node (ref "R15") (pin "2") (pinfunction "2_2") (pintype "passive"))
    )
    (net (code "38") (name "CTRL_DOT2") (class "Default")
      (node (ref "IC3") (pin "30") (pinfunction "(AD7)PA7_30") (pintype "bidirectional"))
      (node (ref "R17") (pin "2") (pinfunction "2_2") (pintype "passive"))
    )
    (net (code "39") (name "DOT1_C") (class "Default")
      (node (ref "N7") (pin "K") (pinfunction "K_K") (pintype "bidirectional"))
      (node (ref "T1") (pin "C") (pinfunction "C_C") (pintype "passive"))
    )
    (net (code "40") (name "DOT2_C") (class "Default")
      (node (ref "N8") (pin "K") (pinfunction "K_K") (pintype "bidirectional"))
      (node (ref "T2") (pin "C") (pinfunction "C_C") (pintype "passive"))
    )
    (net (code "41") (name "GND") (class "Default")
      (node (ref "C1") (pin "2") (pinfunction "2_2") (pintype "passive"))
      (node (ref "C10") (pin "2") (pinfunction "2_2") (pintype "passive"))
      (node (ref "C11") (pin "1") (pinfunction "1_1") (pintype "passive"))
      (node (ref "C12") (pin "1") (pinfunction "1_1") (pintype "passive"))
      (node (ref "C13") (pin "1") (pinfunction "1_1") (pintype "passive"))
      (node (ref "C14") (pin "-") (pinfunction "-_-") (pintype "passive"))
      (node (ref "C15") (pin "2") (pinfunction "2_2") (pintype "passive"))
      (node (ref "C2") (pin "2") (pinfunction "2_2") (pintype "passive"))
      (node (ref "C3") (pin "-") (pinfunction "-_-") (pintype "passive"))
      (node (ref "C4") (pin "-") (pinfunction "-_-") (pintype "passive"))
      (node (ref "C5") (pin "2") (pinfunction "2_2") (pintype "passive"))
      (node (ref "C6") (pin "2") (pinfunction "2_2") (pintype "passive"))
      (node (ref "C7") (pin "2") (pinfunction "2_2") (pintype "passive"))
      (node (ref "C8") (pin "-") (pinfunction "-_-") (pintype "passive"))
      (node (ref "C9") (pin "2") (pinfunction "2_2") (pintype "passive"))
      (node (ref "D14") (pin "A") (pinfunction "A_A") (pintype "passive"))
      (node (ref "GND-1WIRE") (pin "1") (pinfunction "P_1") (pintype "passive"))
      (node (ref "GND-UART") (pin "1") (pinfunction "P_1") (pintype "passive"))
      (node (ref "IC1") (pin "2") (pinfunction "GND_2") (pintype "input"))
      (node (ref "IC2") (pin "4") (pinfunction "GND_4") (pintype "passive"))
      (node (ref "IC3") (pin "16") (pinfunction "GND_16") (pintype "power_in"))
      (node (ref "J1") (pin "3") (pinfunction "3_3") (pintype "passive"))
      (node (ref "JP1") (pin "2") (pinfunction "2_2") (pintype "passive"))
      (node (ref "JP3") (pin "6") (pinfunction "6_6") (pintype "passive"))
      (node (ref "Q1") (pin "3") (pinfunction "S_3") (pintype "passive"))
      (node (ref "R1") (pin "1") (pinfunction "1_1") (pintype "passive"))
      (node (ref "R10") (pin "1") (pinfunction "1_1") (pintype "passive"))
      (node (ref "R11") (pin "1") (pinfunction "1_1") (pintype "passive"))
      (node (ref "R16") (pin "1") (pinfunction "1_1") (pintype "passive"))
      (node (ref "R18") (pin "1") (pinfunction "1_1") (pintype "passive"))
      (node (ref "R4") (pin "1") (pinfunction "1_1") (pintype "passive"))
      (node (ref "R52") (pin "1") (pinfunction "1_1") (pintype "passive"))
      (node (ref "R9") (pin "1") (pinfunction "1_1") (pintype "passive"))
      (node (ref "S1") (pin "3") (pinfunction "P_3") (pintype "passive"))
      (node (ref "S2") (pin "3") (pinfunction "P_3") (pintype "passive"))
      (node (ref "T1") (pin "E") (pinfunction "E_E") (pintype "passive"))
      (node (ref "T10") (pin "E") (pinfunction "E_E") (pintype "passive"))
      (node (ref "T11") (pin "E") (pinfunction "E_E") (pintype "passive"))
      (node (ref "T12") (pin "E") (pinfunction "E_E") (pintype "passive"))
      (node (ref "T2") (pin "E") (pinfunction "E_E") (pintype "passive"))
      (node (ref "T3") (pin "E") (pinfunction "E_E") (pintype "passive"))
      (node (ref "T4") (pin "E") (pinfunction "E_E") (pintype "passive"))
      (node (ref "T5") (pin "E") (pinfunction "E_E") (pintype "passive"))
      (node (ref "T6") (pin "E") (pinfunction "E_E") (pintype "passive"))
      (node (ref "T7") (pin "E") (pinfunction "E_E") (pintype "passive"))
      (node (ref "T8") (pin "E") (pinfunction "E_E") (pintype "passive"))
      (node (ref "T9") (pin "E") (pinfunction "E_E") (pintype "passive"))
      (node (ref "U1") (pin "4") (pinfunction "VSS_4") (pintype "bidirectional"))
      (node (ref "U2") (pin "P$3") (pinfunction "C_P$3") (pintype "passive"))
      (node (ref "U3") (pin "P$3") (pinfunction "C_P$3") (pintype "passive"))
      (node (ref "U4") (pin "P$3") (pinfunction "C_P$3") (pintype "passive"))
      (node (ref "U5") (pin "P$3") (pinfunction "C_P$3") (pintype "passive"))
      (node (ref "U6") (pin "P$3") (pinfunction "C_P$3") (pintype "passive"))
      (node (ref "U7") (pin "P$3") (pinfunction "C_P$3") (pintype "passive"))
    )
    (net (code "42") (name "HV") (class "Default")
      (node (ref "C8") (pin "+") (pinfunction "+_+") (pintype "passive"))
      (node (ref "D1") (pin "C") (pinfunction "C_C") (pintype "passive"))
      (node (ref "R13") (pin "2") (pinfunction "2_2") (pintype "passive"))
      (node (ref "R14") (pin "2") (pinfunction "2_2") (pintype "passive"))
      (node (ref "R2") (pin "2") (pinfunction "2_2") (pintype "passive"))
      (node (ref "R40") (pin "2") (pinfunction "2_2") (pintype "passive"))
      (node (ref "R42") (pin "2") (pinfunction "2_2") (pintype "passive"))
      (node (ref "R44") (pin "2") (pinfunction "2_2") (pintype "passive"))
      (node (ref "R46") (pin "2") (pinfunction "2_2") (pintype "passive"))
      (node (ref "R48") (pin "2") (pinfunction "2_2") (pintype "passive"))
      (node (ref "R50") (pin "2") (pinfunction "2_2") (pintype "passive"))
      (node (ref "R51") (pin "2") (pinfunction "2_2") (pintype "passive"))
    )
    (net (code "43") (name "LED2") (class "Default")
      (node (ref "IC3") (pin "10") (pinfunction "(XCK)PD4_10") (pintype "bidirectional"))
      (node (ref "LED2") (pin "A") (pinfunction "A_A") (pintype "passive"))
    )
    (net (code "44") (name "LED3") (class "Default")
      (node (ref "IC3") (pin "11") (pinfunction "(OC1A)PD5_11") (pintype "bidirectional"))
      (node (ref "LED3") (pin "A") (pinfunction "A_A") (pintype "passive"))
    )
    (net (code "45") (name "MISO") (class "Default")
      (node (ref "IC3") (pin "2") (pinfunction "(MISO)PB6_2") (pintype "bidirectional"))
      (node (ref "JP3") (pin "1") (pinfunction "1_1") (pintype "passive"))
    )
    (net (code "46") (name "MOSI") (class "Default")
      (node (ref "IC3") (pin "1") (pinfunction "(MOSI)PB5_1") (pintype "bidirectional"))
      (node (ref "JP3") (pin "4") (pinfunction "4_4") (pintype "passive"))
    )
    (net (code "47") (name "Net-(C15-Pad1)") (class "Default")
      (node (ref "C15") (pin "1") (pinfunction "1_1") (pintype "passive"))
      (node (ref "D10") (pin "C") (pinfunction "C_C") (pintype "passive"))
      (node (ref "D11") (pin "C") (pinfunction "C_C") (pintype "passive"))
      (node (ref "D12") (pin "C") (pinfunction "C_C") (pintype "passive"))
      (node (ref "D13") (pin "C") (pinfunction "C_C") (pintype "passive"))
      (node (ref "D4") (pin "C") (pinfunction "C_C") (pintype "passive"))
      (node (ref "D5") (pin "C") (pinfunction "C_C") (pintype "passive"))
      (node (ref "D6") (pin "C") (pinfunction "C_C") (pintype "passive"))
      (node (ref "D7") (pin "C") (pinfunction "C_C") (pintype "passive"))
      (node (ref "D8") (pin "C") (pinfunction "C_C") (pintype "passive"))
      (node (ref "D9") (pin "C") (pinfunction "C_C") (pintype "passive"))
      (node (ref "R51") (pin "1") (pinfunction "1_1") (pintype "passive"))
      (node (ref "R52") (pin "2") (pinfunction "2_2") (pintype "passive"))
    )
    (net (code "48") (name "Net-(D2--)") (class "Default")
      (node (ref "C10") (pin "1") (pinfunction "1_1") (pintype "passive"))
      (node (ref "D2") (pin "2") (pinfunction "-_2") (pintype "bidirectional"))
      (node (ref "D3") (pin "2") (pinfunction "-_2") (pintype "bidirectional"))
      (node (ref "U1") (pin "8") (pinfunction "VDD_8") (pintype "bidirectional"))
    )
    (net (code "49") (name "Net-(D3-+)") (class "Default")
      (node (ref "D3") (pin "1") (pinfunction "+_1") (pintype "bidirectional"))
      (node (ref "JP1") (pin "1") (pinfunction "1_1") (pintype "passive"))
    )
    (net (code "50") (name "Net-(IC2-FB)") (class "Default")
      (node (ref "C6") (pin "1") (pinfunction "1_1") (pintype "passive"))
      (node (ref "IC2") (pin "5") (pinfunction "FB_5") (pintype "passive"))
      (node (ref "R3") (pin "S") (pinfunction "S_S") (pintype "passive"))
    )
    (net (code "51") (name "Net-(IC2-SWE)") (class "Default")
      (node (ref "D14") (pin "C") (pinfunction "C_C") (pintype "passive"))
      (node (ref "IC2") (pin "2") (pinfunction "SWE_2") (pintype "passive"))
      (node (ref "Q1") (pin "1") (pinfunction "G_1") (pintype "passive"))
      (node (ref "R1") (pin "2") (pinfunction "2_2") (pintype "passive"))
    )
    (net (code "52") (name "Net-(IC2-TC)") (class "Default")
      (node (ref "C7") (pin "1") (pinfunction "1_1") (pintype "passive"))
      (node (ref "IC2") (pin "3") (pinfunction "TC_3") (pintype "passive"))
    )
    (net (code "53") (name "Net-(IC3-XTAL1)") (class "Default")
      (node (ref "C12") (pin "2") (pinfunction "2_2") (pintype "passive"))
      (node (ref "IC3") (pin "15") (pinfunction "XTAL1_15") (pintype "bidirectional"))
      (node (ref "Q2") (pin "1") (pinfunction "1_1") (pintype "passive"))
    )
    (net (code "54") (name "Net-(IC3-XTAL2)") (class "Default")
      (node (ref "C11") (pin "2") (pinfunction "2_2") (pintype "passive"))
      (node (ref "IC3") (pin "14") (pinfunction "XTAL2_14") (pintype "bidirectional"))
      (node (ref "Q2") (pin "3") (pinfunction "2_3") (pintype "passive"))
    )
    (net (code "55") (name "Net-(LED1-PadC)") (class "Default")
      (node (ref "LED1") (pin "C") (pinfunction "C_C") (pintype "passive"))
      (node (ref "R9") (pin "2") (pinfunction "2_2") (pintype "passive"))
    )
    (net (code "56") (name "Net-(LED2-PadC)") (class "Default")
      (node (ref "LED2") (pin "C") (pinfunction "C_C") (pintype "passive"))
      (node (ref "R10") (pin "2") (pinfunction "2_2") (pintype "passive"))
    )
    (net (code "57") (name "Net-(LED3-PadC)") (class "Default")
      (node (ref "LED3") (pin "C") (pinfunction "C_C") (pintype "passive"))
      (node (ref "R11") (pin "2") (pinfunction "2_2") (pintype "passive"))
    )
    (net (code "58") (name "Net-(N7-PadA)") (class "Default")
      (node (ref "N7") (pin "A") (pinfunction "A_A") (pintype "bidirectional"))
      (node (ref "R13") (pin "1") (pinfunction "1_1") (pintype "passive"))
    )
    (net (code "59") (name "Net-(N8-PadA)") (class "Default")
      (node (ref "N8") (pin "A") (pinfunction "A_A") (pintype "bidirectional"))
      (node (ref "R14") (pin "1") (pinfunction "1_1") (pintype "passive"))
    )
    (net (code "60") (name "Net-(Q1-D)") (class "Default")
      (node (ref "D1") (pin "A") (pinfunction "A_A") (pintype "passive"))
      (node (ref "L1") (pin "2") (pinfunction "2_2") (pintype "passive"))
      (node (ref "Q1") (pin "2") (pinfunction "D_2") (pintype "passive"))
    )
    (net (code "61") (name "Net-(R2-Pad1)") (class "Default")
      (node (ref "R2") (pin "1") (pinfunction "1_1") (pintype "passive"))
      (node (ref "R3") (pin "A") (pinfunction "A_A") (pintype "passive"))
    )
    (net (code "62") (name "Net-(R3-PadE)") (class "Default")
      (node (ref "R3") (pin "E") (pinfunction "E_E") (pintype "passive"))
      (node (ref "R4") (pin "2") (pinfunction "2_2") (pintype "passive"))
    )
    (net (code "63") (name "Net-(R15-Pad1)") (class "Default")
      (node (ref "R15") (pin "1") (pinfunction "1_1") (pintype "passive"))
      (node (ref "R16") (pin "2") (pinfunction "2_2") (pintype "passive"))
      (node (ref "T1") (pin "B") (pinfunction "B_B") (pintype "passive"))
    )
    (net (code "64") (name "Net-(R17-Pad1)") (class "Default")
      (node (ref "R17") (pin "1") (pinfunction "1_1") (pintype "passive"))
      (node (ref "R18") (pin "2") (pinfunction "2_2") (pintype "passive"))
      (node (ref "T2") (pin "B") (pinfunction "B_B") (pintype "passive"))
    )
    (net (code "65") (name "Net-(R19-Pad1)") (class "Default")
      (node (ref "R19") (pin "1") (pinfunction "1_1") (pintype "passive"))
      (node (ref "T3") (pin "B") (pinfunction "B_B") (pintype "passive"))
    )
    (net (code "66") (name "Net-(R21-Pad1)") (class "Default")
      (node (ref "R21") (pin "1") (pinfunction "1_1") (pintype "passive"))
      (node (ref "T4") (pin "B") (pinfunction "B_B") (pintype "passive"))
    )
    (net (code "67") (name "Net-(R23-Pad1)") (class "Default")
      (node (ref "R23") (pin "1") (pinfunction "1_1") (pintype "passive"))
      (node (ref "T5") (pin "B") (pinfunction "B_B") (pintype "passive"))
    )
    (net (code "68") (name "Net-(R25-Pad1)") (class "Default")
      (node (ref "R25") (pin "1") (pinfunction "1_1") (pintype "passive"))
      (node (ref "T6") (pin "B") (pinfunction "B_B") (pintype "passive"))
    )
    (net (code "69") (name "Net-(R27-Pad1)") (class "Default")
      (node (ref "R27") (pin "1") (pinfunction "1_1") (pintype "passive"))
      (node (ref "T7") (pin "B") (pinfunction "B_B") (pintype "passive"))
    )
    (net (code "70") (name "Net-(R29-Pad1)") (class "Default")
      (node (ref "R29") (pin "1") (pinfunction "1_1") (pintype "passive"))
      (node (ref "T8") (pin "B") (pinfunction "B_B") (pintype "passive"))
    )
    (net (code "71") (name "Net-(R31-Pad1)") (class "Default")
      (node (ref "R31") (pin "1") (pinfunction "1_1") (pintype "passive"))
      (node (ref "T9") (pin "B") (pinfunction "B_B") (pintype "passive"))
    )
    (net (code "72") (name "Net-(R33-Pad1)") (class "Default")
      (node (ref "R33") (pin "1") (pinfunction "1_1") (pintype "passive"))
      (node (ref "T10") (pin "B") (pinfunction "B_B") (pintype "passive"))
    )
    (net (code "73") (name "Net-(R35-Pad1)") (class "Default")
      (node (ref "R35") (pin "1") (pinfunction "1_1") (pintype "passive"))
      (node (ref "T11") (pin "B") (pinfunction "B_B") (pintype "passive"))
    )
    (net (code "74") (name "Net-(R37-Pad1)") (class "Default")
      (node (ref "R37") (pin "1") (pinfunction "1_1") (pintype "passive"))
      (node (ref "T12") (pin "B") (pinfunction "B_B") (pintype "passive"))
    )
    (net (code "75") (name "Net-(SW1_PAD1-P)") (class "Default")
      (node (ref "J1") (pin "1") (pinfunction "1_1") (pintype "passive"))
      (node (ref "SW1_PAD1") (pin "1") (pinfunction "P_1") (pintype "passive"))
    )
    (net (code "76") (name "Net-(U1-OSCI)") (class "Default")
      (node (ref "C9") (pin "1") (pinfunction "1_1") (pintype "passive"))
      (node (ref "Q3") (pin "2") (pinfunction "2_2") (pintype "passive"))
      (node (ref "U1") (pin "1") (pinfunction "OSCI_1") (pintype "bidirectional"))
    )
    (net (code "77") (name "Net-(U1-OSCO)") (class "Default")
      (node (ref "Q3") (pin "1") (pinfunction "1_1") (pintype "passive"))
      (node (ref "U1") (pin "2") (pinfunction "OSCO_2") (pintype "bidirectional"))
    )
    (net (code "78") (name "Net-(U2-A)") (class "Default")
      (node (ref "R39") (pin "2") (pinfunction "2_2") (pintype "passive"))
      (node (ref "U2") (pin "P$1") (pinfunction "A_P$1") (pintype "passive"))
    )
    (net (code "79") (name "Net-(U2-COL)") (class "Default")
      (node (ref "R40") (pin "1") (pinfunction "1_1") (pintype "passive"))
      (node (ref "U2") (pin "P$6") (pinfunction "COL_P$6") (pintype "passive"))
    )
    (net (code "80") (name "Net-(U3-A)") (class "Default")
      (node (ref "R41") (pin "2") (pinfunction "2_2") (pintype "passive"))
      (node (ref "U3") (pin "P$1") (pinfunction "A_P$1") (pintype "passive"))
    )
    (net (code "81") (name "Net-(U3-COL)") (class "Default")
      (node (ref "R42") (pin "1") (pinfunction "1_1") (pintype "passive"))
      (node (ref "U3") (pin "P$6") (pinfunction "COL_P$6") (pintype "passive"))
    )
    (net (code "82") (name "Net-(U4-A)") (class "Default")
      (node (ref "R43") (pin "2") (pinfunction "2_2") (pintype "passive"))
      (node (ref "U4") (pin "P$1") (pinfunction "A_P$1") (pintype "passive"))
    )
    (net (code "83") (name "Net-(U4-COL)") (class "Default")
      (node (ref "R44") (pin "1") (pinfunction "1_1") (pintype "passive"))
      (node (ref "U4") (pin "P$6") (pinfunction "COL_P$6") (pintype "passive"))
    )
    (net (code "84") (name "Net-(U5-A)") (class "Default")
      (node (ref "R45") (pin "2") (pinfunction "2_2") (pintype "passive"))
      (node (ref "U5") (pin "P$1") (pinfunction "A_P$1") (pintype "passive"))
    )
    (net (code "85") (name "Net-(U5-COL)") (class "Default")
      (node (ref "R46") (pin "1") (pinfunction "1_1") (pintype "passive"))
      (node (ref "U5") (pin "P$6") (pinfunction "COL_P$6") (pintype "passive"))
    )
    (net (code "86") (name "Net-(U6-A)") (class "Default")
      (node (ref "R47") (pin "2") (pinfunction "2_2") (pintype "passive"))
      (node (ref "U6") (pin "P$1") (pinfunction "A_P$1") (pintype "passive"))
    )
    (net (code "87") (name "Net-(U6-COL)") (class "Default")
      (node (ref "R48") (pin "1") (pinfunction "1_1") (pintype "passive"))
      (node (ref "U6") (pin "P$6") (pinfunction "COL_P$6") (pintype "passive"))
    )
    (net (code "88") (name "Net-(U7-A)") (class "Default")
      (node (ref "R49") (pin "2") (pinfunction "2_2") (pintype "passive"))
      (node (ref "U7") (pin "P$1") (pinfunction "A_P$1") (pintype "passive"))
    )
    (net (code "89") (name "Net-(U7-COL)") (class "Default")
      (node (ref "R50") (pin "1") (pinfunction "1_1") (pintype "passive"))
      (node (ref "U7") (pin "P$6") (pinfunction "COL_P$6") (pintype "passive"))
    )
    (net (code "90") (name "RX") (class "Default")
      (node (ref "IC3") (pin "5") (pinfunction "(RXD)PD0_5") (pintype "bidirectional"))
      (node (ref "RX") (pin "1") (pinfunction "P_1") (pintype "passive"))
    )
    (net (code "91") (name "SCK") (class "Default")
      (node (ref "IC3") (pin "3") (pinfunction "(SCK)PB7_3") (pintype "bidirectional"))
      (node (ref "JP3") (pin "3") (pinfunction "3_3") (pintype "passive"))
    )
    (net (code "92") (name "SCL") (class "Default")
      (node (ref "IC3") (pin "24") (pinfunction "(A14)PC6_24") (pintype "bidirectional"))
      (node (ref "R8") (pin "1") (pinfunction "1_1") (pintype "passive"))
      (node (ref "U1") (pin "6") (pinfunction "SCL_6") (pintype "bidirectional"))
    )
    (net (code "93") (name "SDA") (class "Default")
      (node (ref "IC3") (pin "25") (pinfunction "(A15)PC7_25") (pintype "bidirectional"))
      (node (ref "R7") (pin "1") (pinfunction "1_1") (pintype "passive"))
      (node (ref "U1") (pin "5") (pinfunction "SDA_5") (pintype "bidirectional"))
    )
    (net (code "94") (name "SW1") (class "Default")
      (node (ref "IC3") (pin "13") (pinfunction "(RD)PD7_13") (pintype "bidirectional"))
      (node (ref "S1") (pin "2") (pinfunction "S1_2") (pintype "passive"))
    )
    (net (code "95") (name "SW2") (class "Default")
      (node (ref "IC3") (pin "12") (pinfunction "(WR)PD6_12") (pintype "bidirectional"))
      (node (ref "S2") (pin "2") (pinfunction "S1_2") (pintype "passive"))
    )
    (net (code "96") (name "TX") (class "Default")
      (node (ref "IC3") (pin "7") (pinfunction "(TXD)PD1_7") (pintype "bidirectional"))
      (node (ref "TX") (pin "1") (pinfunction "P_1") (pintype "passive"))
    )
    (net (code "97") (name "unconnected-(IC3-(A13)PC5-Pad23)") (class "Default")
      (node (ref "IC3") (pin "23") (pinfunction "(A13)PC5_23") (pintype "bidirectional"))
    )
    (net (code "98") (name "unconnected-(IC3-NC1-Pad6)") (class "Default")
      (node (ref "IC3") (pin "6") (pinfunction "NC1_6") (pintype "no_connect"))
    )
    (net (code "99") (name "unconnected-(IC3-NC2-Pad17)") (class "Default")
      (node (ref "IC3") (pin "17") (pinfunction "NC2_17") (pintype "no_connect"))
    )
    (net (code "100") (name "unconnected-(IC3-NC3-Pad28)") (class "Default")
      (node (ref "IC3") (pin "28") (pinfunction "NC3_28") (pintype "no_connect"))
    )
    (net (code "101") (name "unconnected-(IC3-NC4-Pad39)") (class "Default")
      (node (ref "IC3") (pin "39") (pinfunction "NC4_39") (pintype "no_connect"))
    )
    (net (code "102") (name "unconnected-(IC3-PE0(ICP{slash}INT2)-Pad29)") (class "Default")
      (node (ref "IC3") (pin "29") (pinfunction "PE0(ICP/INT2)_29") (pintype "bidirectional"))
    )
    (net (code "103") (name "unconnected-(IC3-PE1(ALE)-Pad27)") (class "Default")
      (node (ref "IC3") (pin "27") (pinfunction "PE1(ALE)_27") (pintype "bidirectional"))
    )
    (net (code "104") (name "unconnected-(IC3-PE2(OC1B)-Pad26)") (class "Default")
      (node (ref "IC3") (pin "26") (pinfunction "PE2(OC1B)_26") (pintype "bidirectional"))
    )
    (net (code "105") (name "unconnected-(J1-Pad2)") (class "Default")
      (node (ref "J1") (pin "2") (pinfunction "2_2") (pintype "passive"))
    )
    (net (code "106") (name "unconnected-(N1-RHDP-Pad.)") (class "Default")
      (node (ref "N1") (pin ".") (pinfunction "RHDP_.") (pintype "bidirectional"))
    )
    (net (code "107") (name "unconnected-(N2-RHDP-Pad.)") (class "Default")
      (node (ref "N2") (pin ".") (pinfunction "RHDP_.") (pintype "bidirectional"))
    )
    (net (code "108") (name "unconnected-(N3-RHDP-Pad.)") (class "Default")
      (node (ref "N3") (pin ".") (pinfunction "RHDP_.") (pintype "bidirectional"))
    )
    (net (code "109") (name "unconnected-(N4-RHDP-Pad.)") (class "Default")
      (node (ref "N4") (pin ".") (pinfunction "RHDP_.") (pintype "bidirectional"))
    )
    (net (code "110") (name "unconnected-(N5-RHDP-Pad.)") (class "Default")
      (node (ref "N5") (pin ".") (pinfunction "RHDP_.") (pintype "bidirectional"))
    )
    (net (code "111") (name "unconnected-(N6-RHDP-Pad.)") (class "Default")
      (node (ref "N6") (pin ".") (pinfunction "RHDP_.") (pintype "bidirectional"))
    )
    (net (code "112") (name "unconnected-(S1-P1-Pad4)") (class "Default")
      (node (ref "S1") (pin "4") (pinfunction "P1_4") (pintype "passive"))
    )
    (net (code "113") (name "unconnected-(S1-S-Pad1)") (class "Default")
      (node (ref "S1") (pin "1") (pinfunction "S_1") (pintype "passive"))
    )
    (net (code "114") (name "unconnected-(S2-P1-Pad4)") (class "Default")
      (node (ref "S2") (pin "4") (pinfunction "P1_4") (pintype "passive"))
    )
    (net (code "115") (name "unconnected-(S2-S-Pad1)") (class "Default")
      (node (ref "S2") (pin "1") (pinfunction "S_1") (pintype "passive"))
    )
    (net (code "116") (name "unconnected-(U1-CLKOUT-Pad7)") (class "Default")
      (node (ref "U1") (pin "7") (pinfunction "CLKOUT_7") (pintype "bidirectional"))
    )
    (net (code "117") (name "~{RST}") (class "Default")
      (node (ref "IC3") (pin "4") (pinfunction "RESET_4") (pintype "input"))
      (node (ref "JP3") (pin "5") (pinfunction "5_5") (pintype "passive"))
      (node (ref "R6") (pin "1") (pinfunction "1_1") (pintype "passive"))
    )
  )
)
